# VoltRefBoard.net
KiCad netlist of a schematic drawn in EAGLE
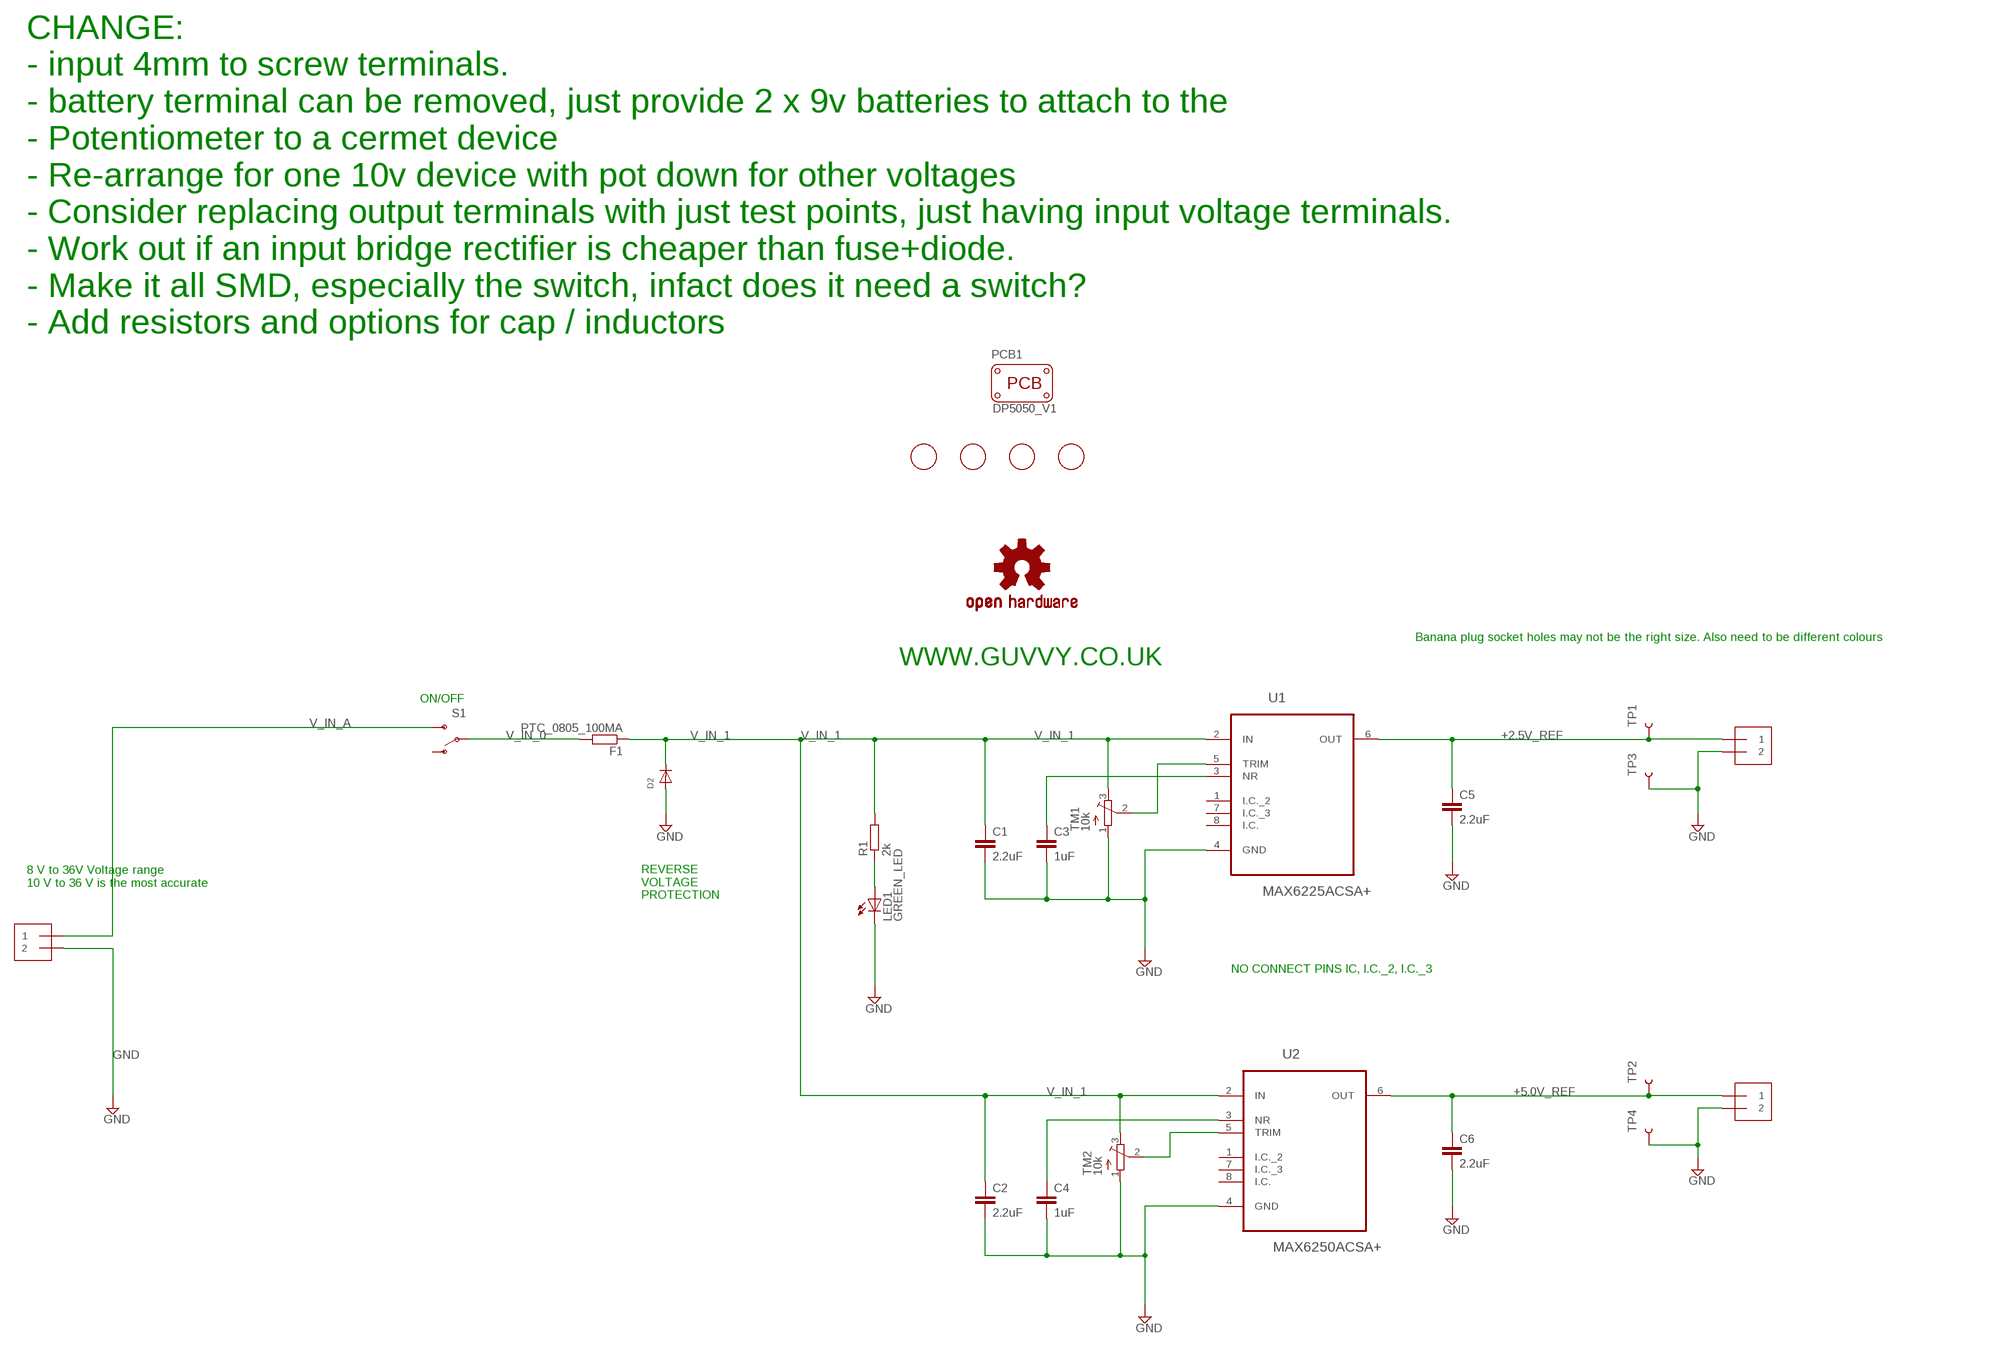
[diagram p0: schematic, sheet 1]

(export (version "E")
  (design (tool "Eeschema 10.0.6"))
  (components
    (comp (ref "C1")
      (value "2.2uF")
      (footprint "eagle-import:C0805")
      (libsource (lib "eagle-import") (part "C-EUC0805"))
    )
    (comp (ref "C2")
      (value "2.2uF")
      (footprint "eagle-import:C0805")
      (libsource (lib "eagle-import") (part "C-EUC0805"))
    )
    (comp (ref "C3")
      (value "1uF")
      (footprint "eagle-import:C0805")
      (libsource (lib "eagle-import") (part "C-EUC0805"))
    )
    (comp (ref "C4")
      (value "1uF")
      (footprint "eagle-import:C0805")
      (libsource (lib "eagle-import") (part "C-EUC0805"))
    )
    (comp (ref "C5")
      (value "2.2uF")
      (footprint "eagle-import:C0805")
      (libsource (lib "eagle-import") (part "C-EUC0805"))
    )
    (comp (ref "C6")
      (value "2.2uF")
      (footprint "eagle-import:C0805")
      (libsource (lib "eagle-import") (part "C-EUC0805"))
    )
    (comp (ref "D2")
      (value "DIODESOD-323F")
      (footprint "eagle-import:SOD-323F")
      (fields (field (name "MF") "NXP") (field (name "MPN") "PMEG3010EJ,115"))
      (libsource (lib "eagle-import") (part "DIODESOD-323F"))
    )
    (comp (ref "F1")
      (value "PTC_0805_100MA")
      (footprint "eagle-import:R0805")
      (fields (field (name "MF") "TE CONNECTIVITY / RAYCHEM") (field (name "MPN") "MINISMDC110F/24-2"))
      (libsource (lib "eagle-import") (part "R-EU_R0805"))
    )
    (comp (ref "J1")
      (value "1X2-3.5MM")
      (footprint "eagle-import:1X2-3.5MM")
      (libsource (lib "eagle-import") (part "1X2-3.5MM"))
    )
    (comp (ref "J2")
      (value "1X2-3.5MM")
      (footprint "eagle-import:1X2-3.5MM")
      (libsource (lib "eagle-import") (part "1X2-3.5MM"))
    )
    (comp (ref "J6")
      (value "1X2-3.5MM")
      (footprint "eagle-import:1X2-3.5MM")
      (libsource (lib "eagle-import") (part "1X2-3.5MM"))
    )
    (comp (ref "LED1")
      (value "GREEN_LED")
      (footprint "eagle-import:P-LCC-2")
      (fields (field (name "MF") "OSRAM") (field (name "MPN") "LGT67K-H2K1-24-Z"))
      (libsource (lib "eagle-import") (part "LEDP-LCC-2"))
    )
    (comp (ref "LOGO1")
      (value "OSHW-LOGOL")
      (footprint "eagle-import:OSHW-LOGO-L")
      (libsource (lib "eagle-import") (part "OSHW-LOGOL"))
    )
    (comp (ref "PCB1")
      (value "PCB_DP_SQUARE-5X5")
      (footprint "eagle-import:DP5050_V1")
      (libsource (lib "eagle-import") (part "PCB_DP_SQUARE-5X5"))
    )
    (comp (ref "R1")
      (value "2k")
      (footprint "eagle-import:R0805")
      (libsource (lib "eagle-import") (part "R-EU_R0805"))
    )
    (comp (ref "S1")
      (value "SWITCH-SPDT-SMD-A")
      (footprint "eagle-import:SWITCH-SPST-SMD-A")
      (libsource (lib "eagle-import") (part "SWITCH-SPDT-SMD-A"))
    )
    (comp (ref "TM1")
      (value "10k")
      (footprint "eagle-import:TC33X")
      (fields (field (name "MF") "VISHAY SFERNICE") (field (name "MPN") "TS53YJ103MR10"))
      (libsource (lib "eagle-import") (part "TRIMPOTTC33X"))
    )
    (comp (ref "TM2")
      (value "10k")
      (footprint "eagle-import:TC33X")
      (fields (field (name "MF") "VISHAY SFERNICE") (field (name "MPN") "TS53YJ103MR10"))
      (libsource (lib "eagle-import") (part "TRIMPOTTC33X"))
    )
    (comp (ref "TP1")
      (value "TP_1MM_TH\"")
      (footprint "eagle-import:TP_1MM_TH")
      (fields (field (name "MF") "MULTICOMP") (field (name "MPN") "TEST-3"))
      (libsource (lib "eagle-import") (part "TP_1MM_TH{dblquote}"))
    )
    (comp (ref "TP2")
      (value "TP_1MM_TH\"")
      (footprint "eagle-import:TP_1MM_TH")
      (fields (field (name "MF") "MULTICOMP") (field (name "MPN") "TEST-3"))
      (libsource (lib "eagle-import") (part "TP_1MM_TH{dblquote}"))
    )
    (comp (ref "TP3")
      (value "TP_1MM_TH\"")
      (footprint "eagle-import:TP_1MM_TH")
      (fields (field (name "MF") "MULTICOMP") (field (name "MPN") "TEST-3"))
      (libsource (lib "eagle-import") (part "TP_1MM_TH{dblquote}"))
    )
    (comp (ref "TP4")
      (value "TP_1MM_TH\"")
      (footprint "eagle-import:TP_1MM_TH")
      (fields (field (name "MF") "MULTICOMP") (field (name "MPN") "TEST-3"))
      (libsource (lib "eagle-import") (part "TP_1MM_TH{dblquote}"))
    )
    (comp (ref "U$1")
      (value "FIDUCIAL")
      (footprint "eagle-import:FIDUCIAL_1MM")
      (libsource (lib "eagle-import") (part "FIDUCIAL"))
    )
    (comp (ref "U$2")
      (value "FIDUCIAL")
      (footprint "eagle-import:FIDUCIAL_1MM")
      (libsource (lib "eagle-import") (part "FIDUCIAL"))
    )
    (comp (ref "U$3")
      (value "FIDUCIAL")
      (footprint "eagle-import:FIDUCIAL_1MM")
      (libsource (lib "eagle-import") (part "FIDUCIAL"))
    )
    (comp (ref "U$4")
      (value "FIDUCIAL")
      (footprint "eagle-import:FIDUCIAL_1MM")
      (libsource (lib "eagle-import") (part "FIDUCIAL"))
    )
    (comp (ref "U1")
      (value "MAX6225ACSA+")
      (footprint "eagle-import:SOIC127P600X175-8N")
      (fields
        (field (name "MF") "MAXIM INTEGRATED PRODUCTS")
        (field (name "MPN") "MAX6225ACSA+.")
        (field (name "OC_FARNELL") "2113189")
      )
      (libsource (lib "eagle-import") (part "MAX6225ACSA+"))
    )
    (comp (ref "U2")
      (value "MAX6250ACSA+")
      (footprint "eagle-import:SOIC127P600X175-8N")
      (fields (field (name "MF") "MAXIM INTEGRATED PRODUCTS") (field (name "MPN") "MAX6250ACSA+."))
      (libsource (lib "eagle-import") (part "MAX6250ACSA+"))
    )
  )
  (nets
    (net (code "1") (name "/+2.5V_REF") (class "Default")
      (node (ref "C5") (pin "1") (pinfunction "1_1") (pintype "passive"))
      (node (ref "J1") (pin "1") (pinfunction "1_1") (pintype "passive"))
      (node (ref "TP1") (pin "P$1") (pinfunction "1_P$1") (pintype "bidirectional"))
      (node (ref "U1") (pin "6") (pinfunction "OUT_6") (pintype "output"))
    )
    (net (code "2") (name "/+5.0V_REF") (class "Default")
      (node (ref "C6") (pin "1") (pinfunction "1_1") (pintype "passive"))
      (node (ref "J2") (pin "1") (pinfunction "1_1") (pintype "passive"))
      (node (ref "TP2") (pin "P$1") (pinfunction "1_P$1") (pintype "bidirectional"))
      (node (ref "U2") (pin "6") (pinfunction "OUT_6") (pintype "output"))
    )
    (net (code "3") (name "/V_IN_0") (class "Default")
      (node (ref "F1") (pin "2") (pinfunction "2_2") (pintype "passive"))
      (node (ref "S1") (pin "2") (pinfunction "P_2") (pintype "passive"))
    )
    (net (code "4") (name "/V_IN_1") (class "Default")
      (node (ref "C1") (pin "1") (pinfunction "1_1") (pintype "passive"))
      (node (ref "C2") (pin "1") (pinfunction "1_1") (pintype "passive"))
      (node (ref "D2") (pin "C") (pinfunction "C_C") (pintype "passive"))
      (node (ref "F1") (pin "1") (pinfunction "1_1") (pintype "passive"))
      (node (ref "R1") (pin "2") (pinfunction "2_2") (pintype "passive"))
      (node (ref "TM1") (pin "3") (pinfunction "E_3") (pintype "passive"))
      (node (ref "TM2") (pin "3") (pinfunction "E_3") (pintype "passive"))
      (node (ref "U1") (pin "2") (pinfunction "IN_2") (pintype "input"))
      (node (ref "U2") (pin "2") (pinfunction "IN_2") (pintype "power_in"))
    )
    (net (code "5") (name "/V_IN_A") (class "Default")
      (node (ref "J6") (pin "1") (pinfunction "1_1") (pintype "passive"))
      (node (ref "S1") (pin "3") (pinfunction "S_3") (pintype "passive"))
    )
    (net (code "6") (name "GND") (class "Default")
      (node (ref "C1") (pin "2") (pinfunction "2_2") (pintype "passive"))
      (node (ref "C2") (pin "2") (pinfunction "2_2") (pintype "passive"))
      (node (ref "C3") (pin "2") (pinfunction "2_2") (pintype "passive"))
      (node (ref "C4") (pin "2") (pinfunction "2_2") (pintype "passive"))
      (node (ref "C5") (pin "2") (pinfunction "2_2") (pintype "passive"))
      (node (ref "C6") (pin "2") (pinfunction "2_2") (pintype "passive"))
      (node (ref "D2") (pin "A") (pinfunction "A_A") (pintype "passive"))
      (node (ref "J1") (pin "2") (pinfunction "2_2") (pintype "passive"))
      (node (ref "J2") (pin "2") (pinfunction "2_2") (pintype "passive"))
      (node (ref "J6") (pin "2") (pinfunction "2_2") (pintype "passive"))
      (node (ref "LED1") (pin "C") (pinfunction "C_C") (pintype "passive"))
      (node (ref "TM1") (pin "1") (pinfunction "A_1") (pintype "passive"))
      (node (ref "TM2") (pin "1") (pinfunction "A_1") (pintype "passive"))
      (node (ref "TP3") (pin "P$1") (pinfunction "1_P$1") (pintype "bidirectional"))
      (node (ref "TP4") (pin "P$1") (pinfunction "1_P$1") (pintype "bidirectional"))
      (node (ref "U1") (pin "4") (pinfunction "GND_4") (pintype "passive"))
      (node (ref "U2") (pin "4") (pinfunction "GND_4") (pintype "passive"))
    )
    (net (code "7") (name "Net-(LED1-PadA)") (class "Default")
      (node (ref "LED1") (pin "A") (pinfunction "A_A") (pintype "passive"))
      (node (ref "R1") (pin "1") (pinfunction "1_1") (pintype "passive"))
    )
    (net (code "8") (name "Net-(TM1-S)") (class "Default")
      (node (ref "TM1") (pin "2") (pinfunction "S_2") (pintype "passive"))
      (node (ref "U1") (pin "5") (pinfunction "TRIM_5") (pintype "input"))
    )
    (net (code "9") (name "Net-(TM2-S)") (class "Default")
      (node (ref "TM2") (pin "2") (pinfunction "S_2") (pintype "passive"))
      (node (ref "U2") (pin "5") (pinfunction "TRIM_5") (pintype "input"))
    )
    (net (code "10") (name "Net-(U1-NR)") (class "Default")
      (node (ref "C3") (pin "1") (pinfunction "1_1") (pintype "passive"))
      (node (ref "U1") (pin "3") (pinfunction "NR_3") (pintype "input"))
    )
    (net (code "11") (name "Net-(U2-NR)") (class "Default")
      (node (ref "C4") (pin "1") (pinfunction "1_1") (pintype "passive"))
      (node (ref "U2") (pin "3") (pinfunction "NR_3") (pintype "input"))
    )
    (net (code "12") (name "unconnected-(S1-O-Pad1)") (class "Default")
      (node (ref "S1") (pin "1") (pinfunction "O_1") (pintype "passive"))
    )
    (net (code "13") (name "unconnected-(U1-I.C.-Pad8)") (class "Default")
      (node (ref "U1") (pin "8") (pinfunction "I.C._8") (pintype "passive"))
    )
    (net (code "14") (name "unconnected-(U1-I.C._2-Pad1)") (class "Default")
      (node (ref "U1") (pin "1") (pinfunction "I.C._2_1") (pintype "passive"))
    )
    (net (code "15") (name "unconnected-(U1-I.C._3-Pad7)") (class "Default")
      (node (ref "U1") (pin "7") (pinfunction "I.C._3_7") (pintype "passive"))
    )
    (net (code "16") (name "unconnected-(U2-I.C.-Pad8)") (class "Default")
      (node (ref "U2") (pin "8") (pinfunction "I.C._8") (pintype "passive"))
    )
    (net (code "17") (name "unconnected-(U2-I.C._2-Pad1)") (class "Default")
      (node (ref "U2") (pin "1") (pinfunction "I.C._2_1") (pintype "passive"))
    )
    (net (code "18") (name "unconnected-(U2-I.C._3-Pad7)") (class "Default")
      (node (ref "U2") (pin "7") (pinfunction "I.C._3_7") (pintype "passive"))
    )
  )
)
